# IrDA_TFDU6102.net
KiCad netlist of a schematic drawn in Altium Designer
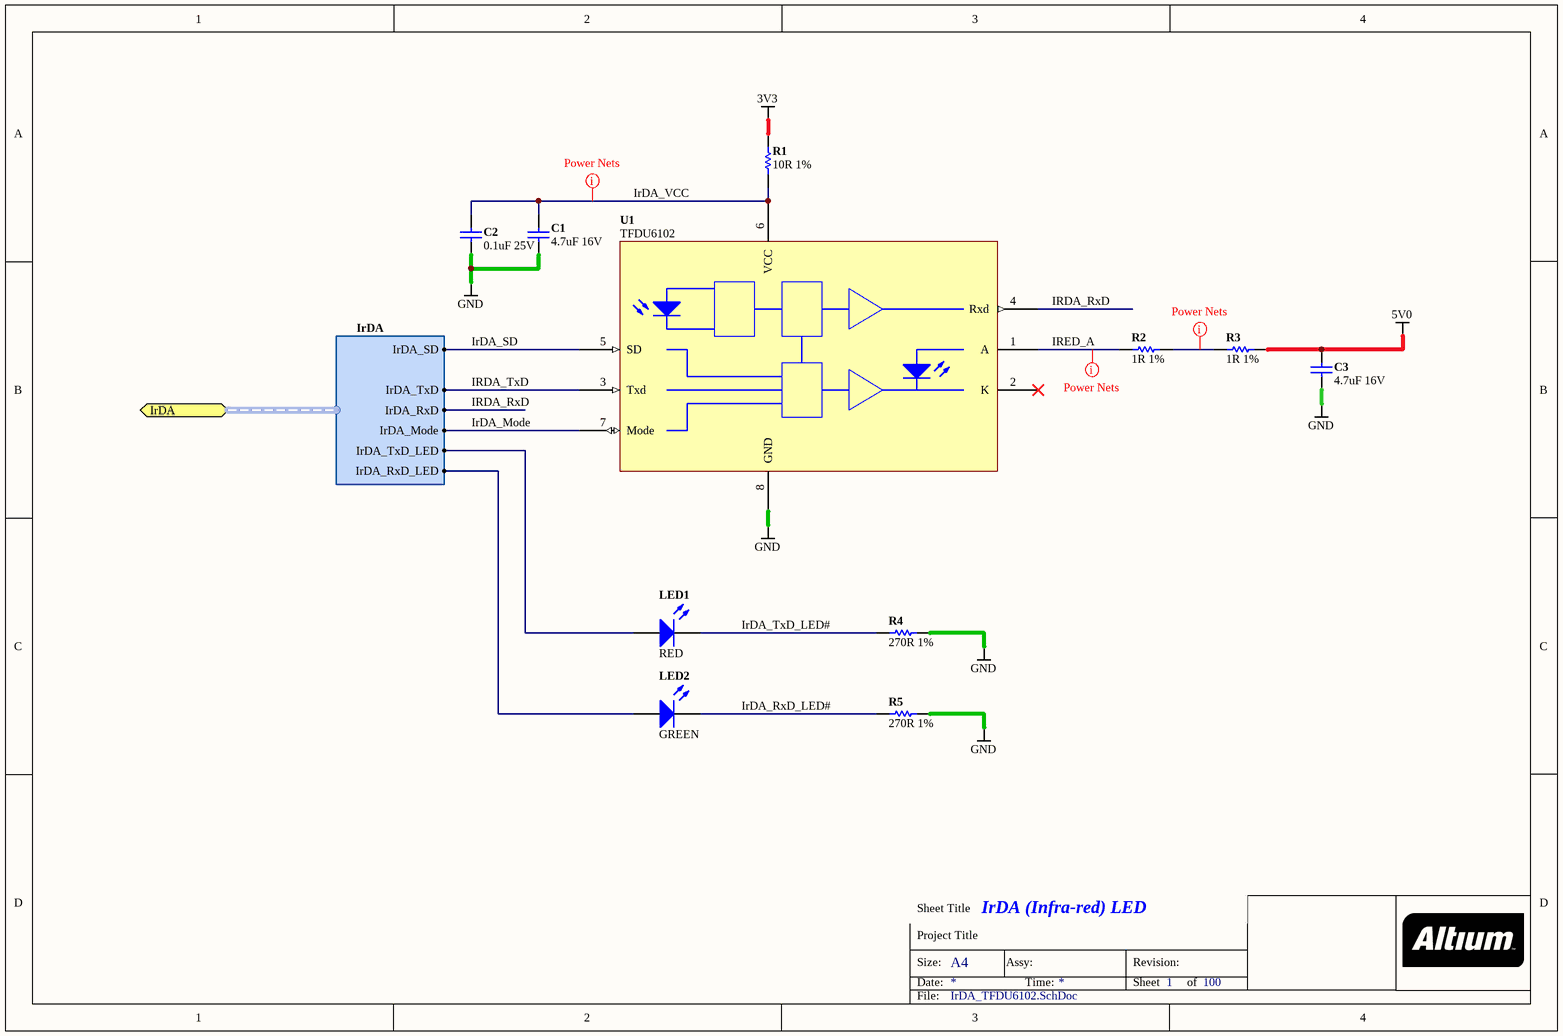
[diagram p0: IrDA_TFDU6102.SchDoc]

(export (version "E")
  (design (tool "Eeschema 10.0.6"))
  (components
    (comp (ref "C1")
      (value "4.7uF 16V")
      (footprint "CAPC2012-STAR")
      (description "Capacitor, Ceramic, 4.7uF 10% 16V 0805 (2012) X7R")
      (fields (field (name "TOLERANCE") "10 %"))
      (libsource (lib "AltiumDesignLibrary") (part "CAP-NP"))
    )
    (comp (ref "C2")
      (value "0.1uF 25V")
      (footprint "CAPC1005-STAR")
      (description "Capacitor, Ceramic, 0.1uF 25V 0402 (1005)")
      (fields (field (name "TOLERANCE") "10 %"))
      (libsource (lib "AltiumDesignLibrary") (part "CAP-NP"))
    )
    (comp (ref "C3")
      (value "4.7uF 16V")
      (footprint "CAPC2012-STAR")
      (description "Capacitor, Ceramic, 4.7uF 10% 16V 0805 (2012) X7R")
      (fields (field (name "TOLERANCE") "10 %"))
      (libsource (lib "AltiumDesignLibrary") (part "CAP-NP"))
    )
    (comp (ref "LED1")
      (value "RED")
      (footprint "LED2012-STAR")
      (description "LED, Red 0805 (2013) HSMH-C170")
      (libsource (lib "AltiumDesignLibrary") (part "DIO-LED-1S"))
    )
    (comp (ref "LED2")
      (value "GREEN")
      (footprint "LED2012-STAR")
      (description "LED, Green 0805 (2012) KP-2012SGD")
      (libsource (lib "AltiumDesignLibrary") (part "DIO-LED-1S"))
    )
    (comp (ref "R1")
      (value "10R 1%")
      (footprint "RESC2012-STAR")
      (description "Resistor, 10R 1% 0805 (2012)")
      (fields (field (name "TOLERANCE") "1 %"))
      (libsource (lib "AltiumDesignLibrary") (part "RES"))
    )
    (comp (ref "R2")
      (value "1R 1%")
      (footprint "RESC2012-STAR")
      (description "Resistor, 1R 1% 0805 (2012)")
      (fields (field (name "TOLERANCE") "1 %"))
      (libsource (lib "AltiumDesignLibrary") (part "RES"))
    )
    (comp (ref "R3")
      (value "1R 1%")
      (footprint "RESC2012-STAR")
      (description "Resistor, 1R 1% 0805 (2012)")
      (fields (field (name "TOLERANCE") "1 %"))
      (libsource (lib "AltiumDesignLibrary") (part "RES"))
    )
    (comp (ref "R4")
      (value "270R 1%")
      (footprint "RESC1005-STAR")
      (description "Resistor, 270R 1% 0402 (1005)")
      (fields (field (name "TOLERANCE") "1 %"))
      (libsource (lib "AltiumDesignLibrary") (part "RES"))
    )
    (comp (ref "R5")
      (value "270R 1%")
      (footprint "RESC1005-STAR")
      (description "Resistor, 270R 1% 0402 (1005)")
      (fields (field (name "TOLERANCE") "1 %"))
      (libsource (lib "AltiumDesignLibrary") (part "RES"))
    )
    (comp (ref "U1")
      (value "TFDU6102")
      (footprint "TFDU6102")
      (description "LED, TFDU6102 Infrared Transceiver up to 4Mbits/s")
      (libsource (lib "AltiumDesignLibrary") (part "TFDU6102"))
    )
  )
  (nets
    (net (code "2") (name "/IRDA_RxD") (class "Default")
      (node (ref "U1") (pin "4") (pinfunction "Rxd_4") (pintype "output"))
    )
    (net (code "3") (name "/IRDA_TxD") (class "Default")
      (node (ref "U1") (pin "3") (pinfunction "Txd_3") (pintype "input"))
    )
    (net (code "4") (name "/IRED_A") (class "Default")
      (node (ref "R2") (pin "1") (pinfunction "1_1") (pintype "passive"))
      (node (ref "U1") (pin "1") (pinfunction "A_1") (pintype "power_in"))
    )
    (net (code "5") (name "/IrDA_Mode") (class "Default")
      (node (ref "U1") (pin "7") (pinfunction "Mode_7") (pintype "bidirectional"))
    )
    (net (code "6") (name "/IrDA_RxD_LED") (class "Default")
      (node (ref "LED2") (pin "1") (pinfunction "A_1") (pintype "passive"))
    )
    (net (code "7") (name "/IrDA_RxD_LED#") (class "Default")
      (node (ref "LED2") (pin "2") (pinfunction "K_2") (pintype "passive"))
      (node (ref "R5") (pin "2") (pinfunction "2_2") (pintype "passive"))
    )
    (net (code "8") (name "/IrDA_SD") (class "Default")
      (node (ref "U1") (pin "5") (pinfunction "SD_5") (pintype "input"))
    )
    (net (code "9") (name "/IrDA_TxD_LED") (class "Default")
      (node (ref "LED1") (pin "1") (pinfunction "A_1") (pintype "passive"))
    )
    (net (code "10") (name "/IrDA_TxD_LED#") (class "Default")
      (node (ref "LED1") (pin "2") (pinfunction "K_2") (pintype "passive"))
      (node (ref "R4") (pin "2") (pinfunction "2_2") (pintype "passive"))
    )
    (net (code "11") (name "/IrDA_VCC") (class "Default")
      (node (ref "C1") (pin "1") (pinfunction "1_1") (pintype "passive"))
      (node (ref "C2") (pin "1") (pinfunction "1_1") (pintype "passive"))
      (node (ref "R1") (pin "1") (pinfunction "1_1") (pintype "passive"))
      (node (ref "U1") (pin "6") (pinfunction "VCC_6") (pintype "power_in"))
    )
    (net (code "13") (name "3V3") (class "Default")
      (node (ref "R1") (pin "2") (pinfunction "2_2") (pintype "passive"))
    )
    (net (code "14") (name "5V0") (class "Default")
      (node (ref "C3") (pin "1") (pinfunction "1_1") (pintype "passive"))
      (node (ref "R3") (pin "2") (pinfunction "2_2") (pintype "passive"))
    )
    (net (code "15") (name "GND") (class "Default")
      (node (ref "C1") (pin "2") (pinfunction "2_2") (pintype "passive"))
      (node (ref "C2") (pin "2") (pinfunction "2_2") (pintype "passive"))
      (node (ref "C3") (pin "2") (pinfunction "2_2") (pintype "passive"))
      (node (ref "R4") (pin "1") (pinfunction "1_1") (pintype "passive"))
      (node (ref "R5") (pin "1") (pinfunction "1_1") (pintype "passive"))
      (node (ref "U1") (pin "8") (pinfunction "GND_8") (pintype "power_in"))
    )
    (net (code "16") (name "Net-(R2-Pad2)") (class "Default")
      (node (ref "R2") (pin "2") (pinfunction "2_2") (pintype "passive"))
      (node (ref "R3") (pin "1") (pinfunction "1_1") (pintype "passive"))
    )
    (net (code "17") (name "unconnected-(U1-K-Pad2)") (class "Default")
      (node (ref "U1") (pin "2") (pinfunction "K_2") (pintype "passive+no_connect"))
    )
  )
)
